# H2BR0.net
KiCad netlist of a schematic drawn in EAGLE
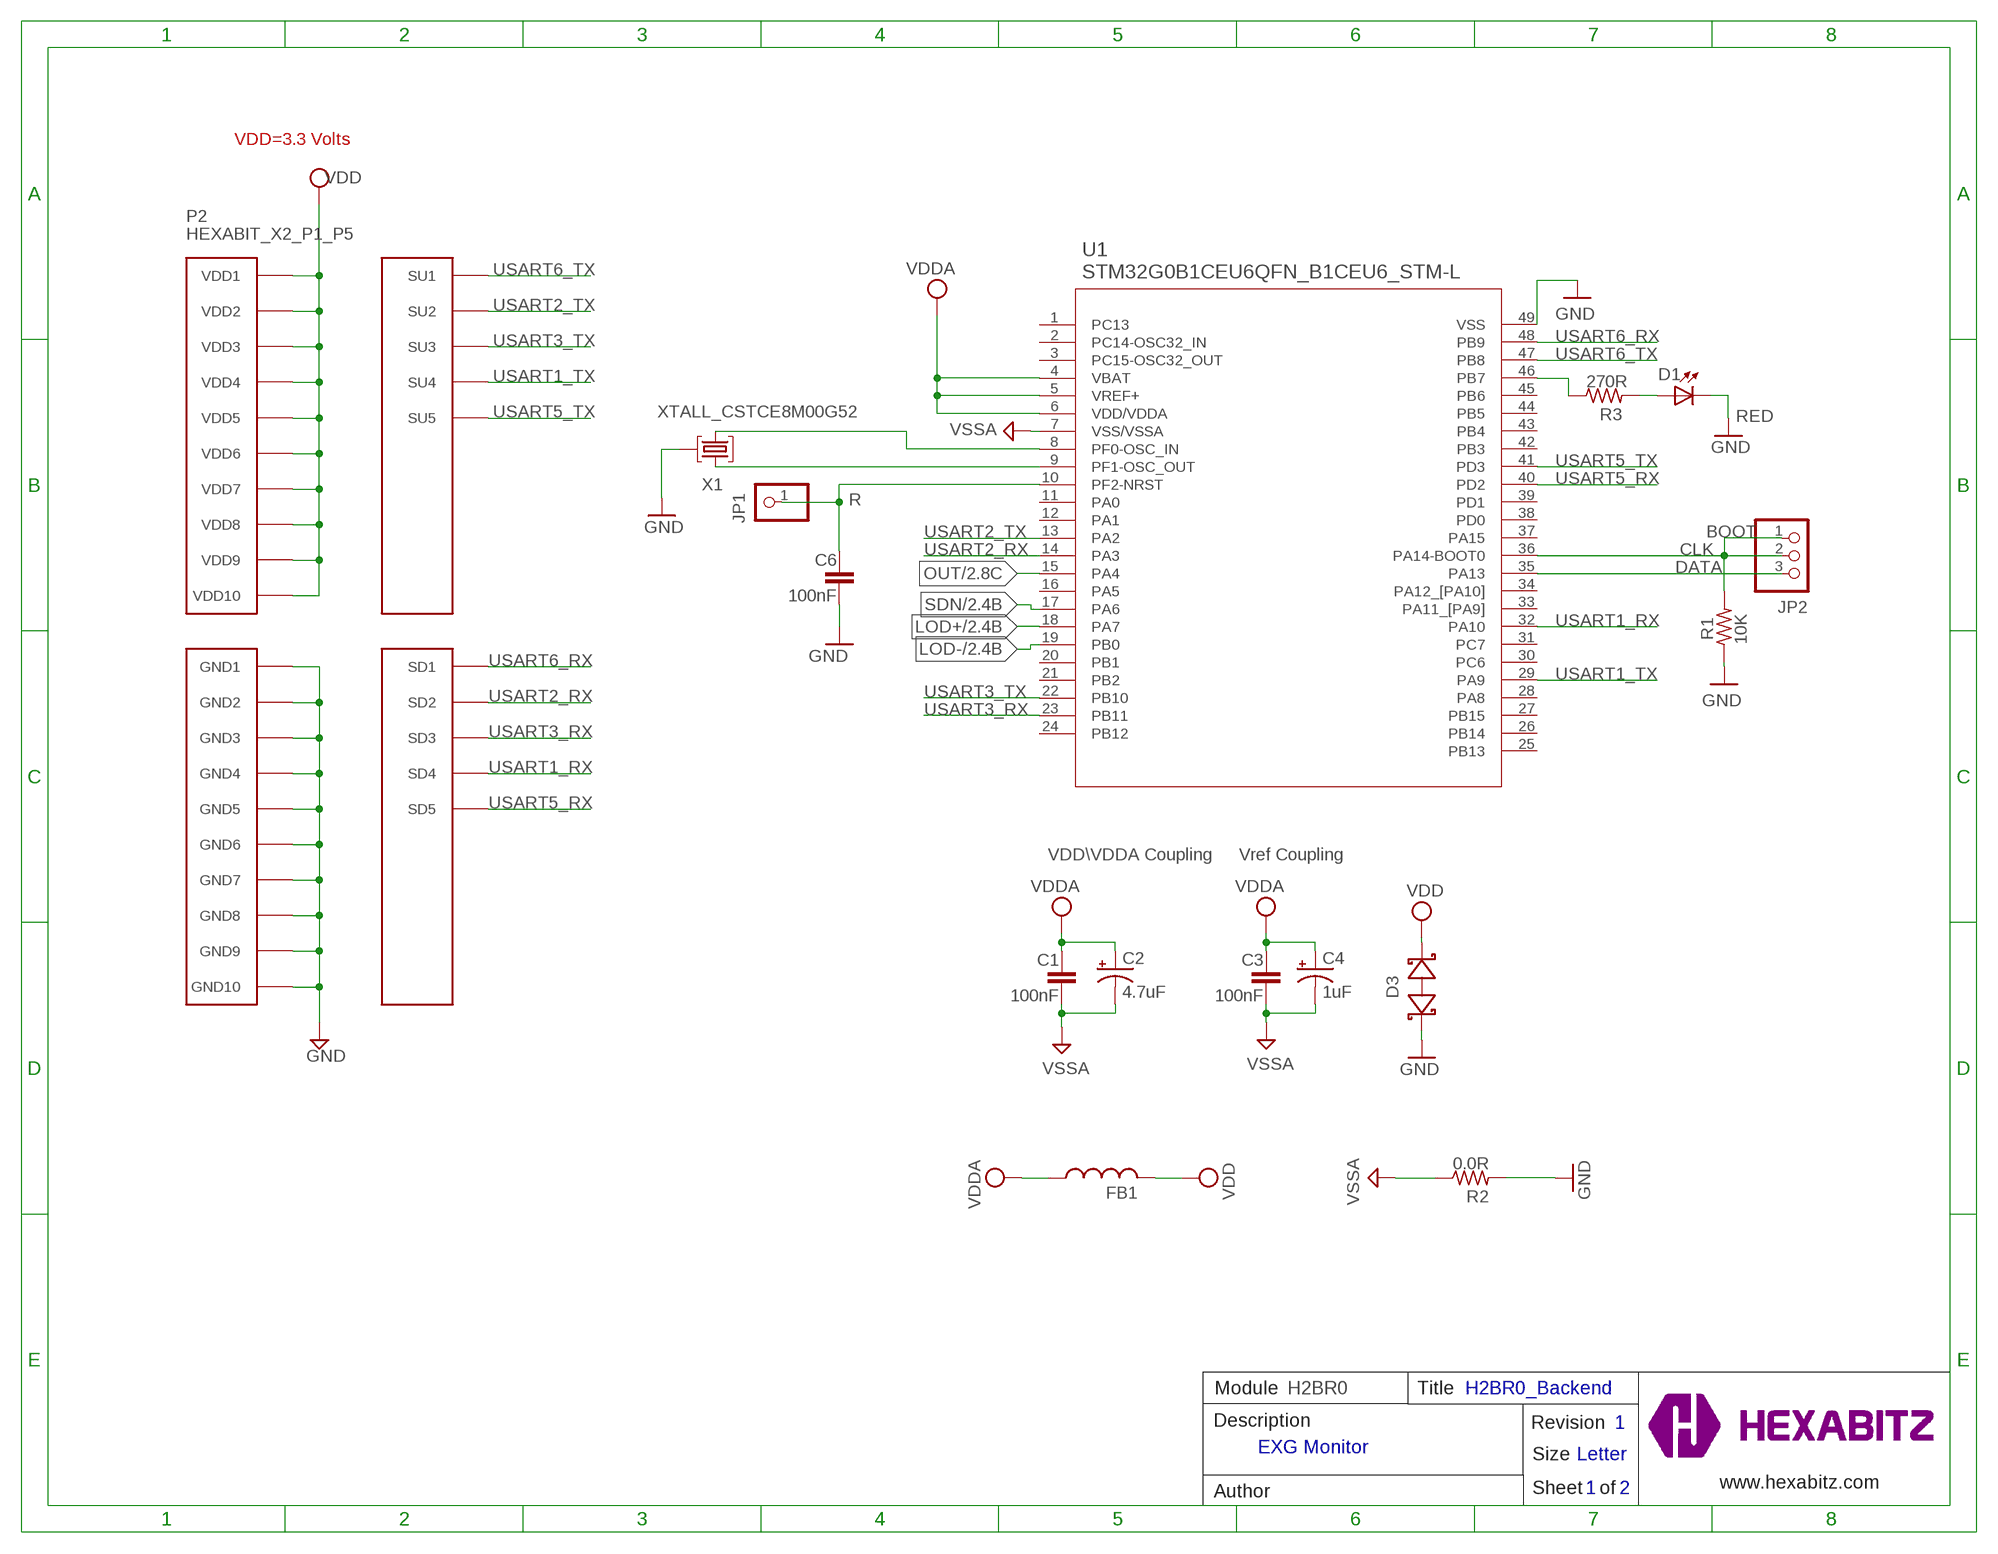
[diagram p0: schematic, sheet 1]
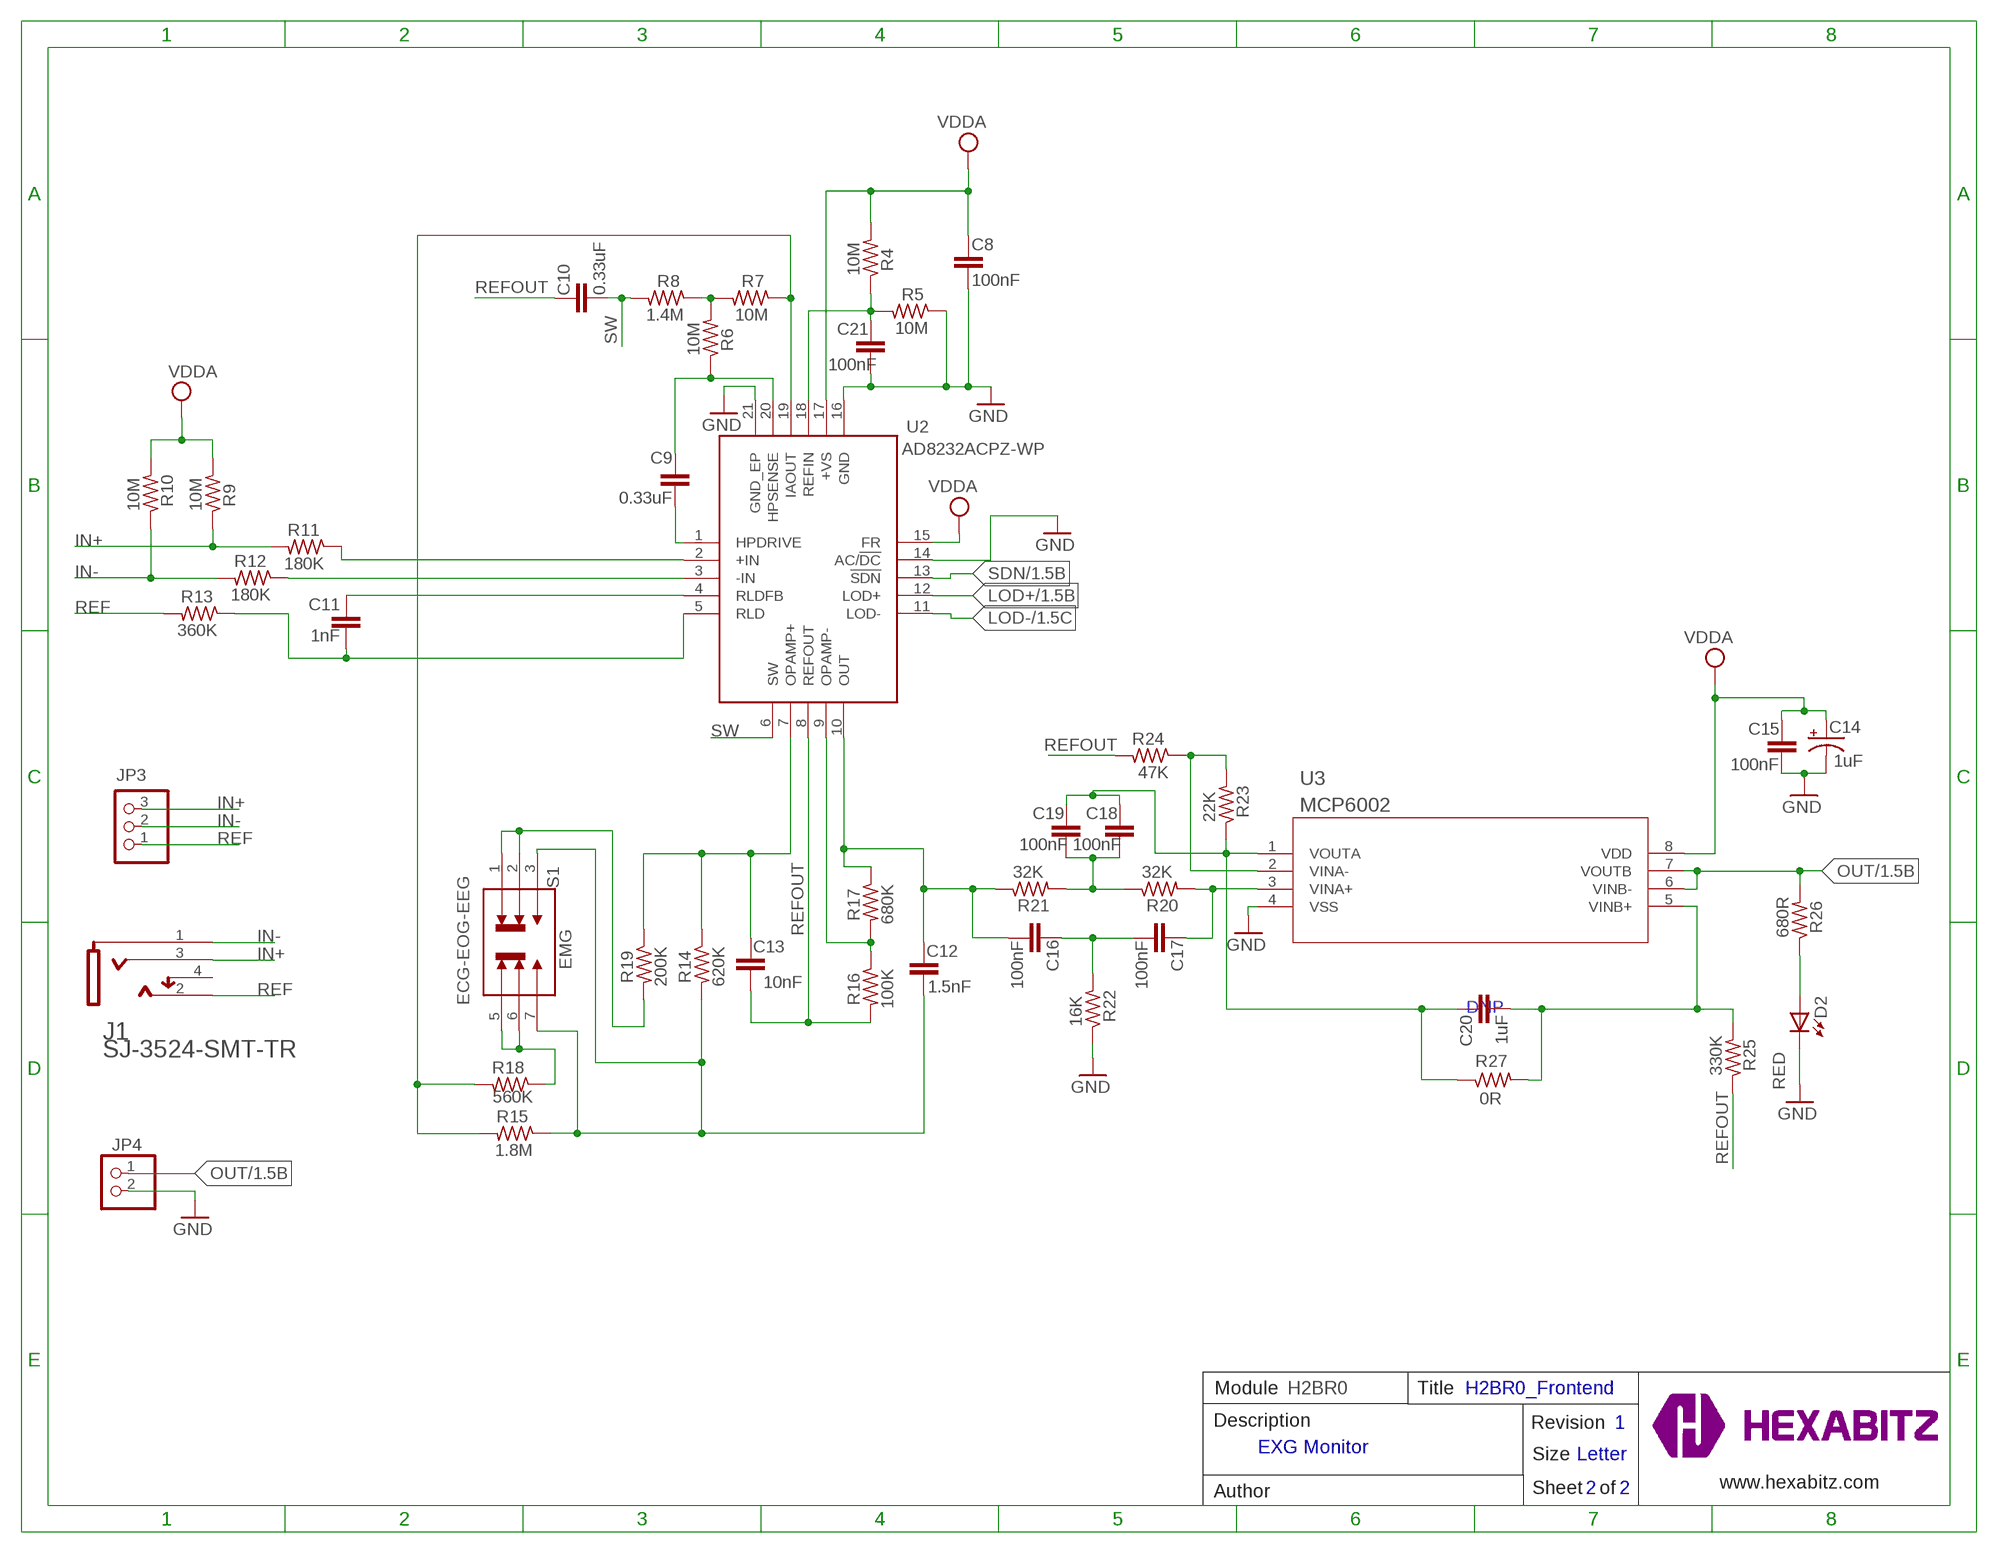
[diagram p1: schematic, sheet 2]

(export (version "E")
  (design (tool "Eeschema 10.0.6"))
  (components
    (comp (ref "C1")
      (value "100nF")
      (footprint "eagle-import:C-0603")
      (libsource (lib "eagle-import") (part "C-0603"))
    )
    (comp (ref "C2")
      (value "4.7uF")
      (footprint "eagle-import:C-0805-POL")
      (libsource (lib "eagle-import") (part "C-0805-POL"))
    )
    (comp (ref "C3")
      (value "100nF")
      (footprint "eagle-import:C-0603")
      (libsource (lib "eagle-import") (part "C-0603"))
    )
    (comp (ref "C4")
      (value "1uF")
      (footprint "eagle-import:C-0805-POL")
      (libsource (lib "eagle-import") (part "C-0805-POL"))
    )
    (comp (ref "C6")
      (value "100nF")
      (footprint "eagle-import:C-0603")
      (libsource (lib "eagle-import") (part "C-0603"))
    )
    (comp (ref "D1")
      (value "RED")
      (footprint "eagle-import:VLMS1300-GS08")
      (fields
        (field (name "MPN") "VLMS1300-GS08")
        (field (name "MFN") "Vishay")
        (field (name "MPN_1") "VLMS1300-GS08")
        (field (name "OCTOPART_URL") "https://octopart.com/vlms1300-gs08-vishay-21709201?r=sp&s=_gcP4_q8T1SC6PJQPTQ9yA")
      )
      (libsource (lib "eagle-import") (part "VLMS1300-GS08"))
    )
    (comp (ref "D3")
      (value "BOURNS_CDSOD323-T03SCBOURNS_CDSOD323-T03SC_0_0")
      (footprint "eagle-import:BOURNS_CDSOD323-T03SC_0")
      (fields (field (name "MPN") "CDSOD323-T03SC"))
      (libsource (lib "eagle-import") (part "BOURNS_CDSOD323-T03SCBOURNS_CDSOD323-T03SC_0_0"))
    )
    (comp (ref "FB1")
      (value "FB-0603")
      (footprint "eagle-import:FB-0603")
      (libsource (lib "eagle-import") (part "FB-0603"))
    )
    (comp (ref "JP1")
      (value "R")
      (footprint "eagle-import:1X01")
      (fields (field (name "MPN") "87227-1"))
      (libsource (lib "eagle-import") (part "PINHD-1X1"))
    )
    (comp (ref "JP2")
      (value "PINHD-1X3")
      (footprint "eagle-import:1X03")
      (libsource (lib "eagle-import") (part "PINHD-1X3"))
    )
    (comp (ref "P2")
      (value "HEXABIT_X2_P1_P5")
      (footprint "eagle-import:HEXABIT_17.32_X2_P1_P5")
      (libsource (lib "eagle-import") (part "HEXABIT_X2_P1_P5"))
    )
    (comp (ref "R1")
      (value "10K")
      (footprint "eagle-import:R-0603")
      (libsource (lib "eagle-import") (part "R-0603"))
    )
    (comp (ref "R2")
      (value "0.0R")
      (footprint "eagle-import:R-0603")
      (libsource (lib "eagle-import") (part "R-0603"))
    )
    (comp (ref "R3")
      (value "270R")
      (footprint "eagle-import:R-0603")
      (libsource (lib "eagle-import") (part "R-0603"))
    )
    (comp (ref "TRIMBLE-LOGO2")
      (value "HEXA-LOGO")
      (footprint "eagle-import:HEXA-LOGO")
      (libsource (lib "eagle-import") (part "HEXA-LOGO"))
    )
    (comp (ref "U1")
      (value "STM32G0B1CEU6QFN_B1CEU6_STM-L")
      (footprint "eagle-import:QFN_B1CEU6_STM-L")
      (fields
        (field (name "MANUFACTURER_PART_NUMBER") "STM32G0B1CEU6")
        (field (name "COPYRIGHT") "Copyright (C) 2021 Ultra Librarian. All rights reserved.")
      )
      (libsource (lib "eagle-import") (part "STM32G0B1CEU6QFN_B1CEU6_STM-L"))
    )
    (comp (ref "X1")
      (value "XTALL_CSTCE8M00G52")
      (footprint "eagle-import:XTALL_CSTCE8M00G52")
      (fields (field (name "MPN") "CSTCE8M00G52Z-R0"))
      (libsource (lib "eagle-import") (part "XTALL_CSTCE8M00G52"))
    )
    (comp (ref "C8")
      (value "100nF")
      (footprint "eagle-import:C-0603")
      (libsource (lib "eagle-import") (part "C-0603"))
    )
    (comp (ref "C9")
      (value "0.33uF")
      (footprint "eagle-import:C-0603")
      (libsource (lib "eagle-import") (part "C-0603"))
    )
    (comp (ref "C10")
      (value "0.33uF")
      (footprint "eagle-import:C-0603")
      (libsource (lib "eagle-import") (part "C-0603"))
    )
    (comp (ref "C11")
      (value "1nF")
      (footprint "eagle-import:C-0603")
      (libsource (lib "eagle-import") (part "C-0603"))
    )
    (comp (ref "C12")
      (value "1.5nF")
      (footprint "eagle-import:C-0603")
      (libsource (lib "eagle-import") (part "C-0603"))
    )
    (comp (ref "C13")
      (value "10nF")
      (footprint "eagle-import:C-0603")
      (libsource (lib "eagle-import") (part "C-0603"))
    )
    (comp (ref "C14")
      (value "1uF")
      (footprint "eagle-import:C-0805-POL")
      (libsource (lib "eagle-import") (part "C-0805-POL"))
    )
    (comp (ref "C15")
      (value "100nF")
      (footprint "eagle-import:C-0603")
      (libsource (lib "eagle-import") (part "C-0603"))
    )
    (comp (ref "C16")
      (value "100nF")
      (footprint "eagle-import:C-0603")
      (libsource (lib "eagle-import") (part "C-0603"))
    )
    (comp (ref "C17")
      (value "100nF")
      (footprint "eagle-import:C-0603")
      (libsource (lib "eagle-import") (part "C-0603"))
    )
    (comp (ref "C18")
      (value "100nF")
      (footprint "eagle-import:C-0603")
      (libsource (lib "eagle-import") (part "C-0603"))
    )
    (comp (ref "C19")
      (value "100nF")
      (footprint "eagle-import:C-0603")
      (libsource (lib "eagle-import") (part "C-0603"))
    )
    (comp (ref "C20")
      (value "1uF")
      (footprint "eagle-import:C-0603")
      (fields (field (name "MPN") "GRM188R61A105KA61J"))
      (libsource (lib "eagle-import") (part "C-0603"))
    )
    (comp (ref "C21")
      (value "100nF")
      (footprint "eagle-import:C-0603")
      (libsource (lib "eagle-import") (part "C-0603"))
    )
    (comp (ref "D2")
      (value "RED")
      (footprint "eagle-import:VLMS1300-GS08")
      (fields
        (field (name "MPN") "VLMS1300-GS08")
        (field (name "MFN") "Vishay")
        (field (name "MPN_1") "VLMS1300-GS08")
        (field (name "OCTOPART_URL") "https://octopart.com/vlms1300-gs08-vishay-21709201?r=sp&s=_gcP4_q8T1SC6PJQPTQ9yA")
      )
      (libsource (lib "eagle-import") (part "VLMS1300-GS08"))
    )
    (comp (ref "J1")
      (value "CUI_DEVICES_SJ-3524-SMT-TRCUI_DEVICES_SJ-3524-SMT-TR_0_0")
      (footprint "eagle-import:CUI_DEVICES_SJ-3524-SMT-TR_0")
      (fields
        (field (name "DIGIKEY_PART_NUMBER") "CP-3524SJCT-ND")
        (field (name "MOUSER_PART_NUMBER") "490-SJ-3524-SMT-TR")
        (field (name "MPN") "SJ-3524-SMT-TR")
      )
      (libsource (lib "eagle-import") (part "CUI_DEVICES_SJ-3524-SMT-TRCUI_DEVICES_SJ-3524-SMT-TR_0_0"))
    )
    (comp (ref "JP3")
      (value "PINHD-1X3")
      (footprint "eagle-import:1X03")
      (libsource (lib "eagle-import") (part "PINHD-1X3"))
    )
    (comp (ref "JP4")
      (value "PINHD-1X2(ROUND)")
      (footprint "eagle-import:1X02")
      (libsource (lib "eagle-import") (part "PINHD-1X2(ROUND)"))
    )
    (comp (ref "R4")
      (value "10M")
      (footprint "eagle-import:R-0603")
      (libsource (lib "eagle-import") (part "R-0603"))
    )
    (comp (ref "R5")
      (value "10M")
      (footprint "eagle-import:R-0603")
      (libsource (lib "eagle-import") (part "R-0603"))
    )
    (comp (ref "R6")
      (value "10M")
      (footprint "eagle-import:R-0603")
      (libsource (lib "eagle-import") (part "R-0603"))
    )
    (comp (ref "R7")
      (value "10M")
      (footprint "eagle-import:R-0603")
      (libsource (lib "eagle-import") (part "R-0603"))
    )
    (comp (ref "R8")
      (value "1.4M")
      (footprint "eagle-import:R-0603")
      (libsource (lib "eagle-import") (part "R-0603"))
    )
    (comp (ref "R9")
      (value "10M")
      (footprint "eagle-import:R-0603")
      (libsource (lib "eagle-import") (part "R-0603"))
    )
    (comp (ref "R10")
      (value "10M")
      (footprint "eagle-import:R-0603")
      (libsource (lib "eagle-import") (part "R-0603"))
    )
    (comp (ref "R11")
      (value "180K")
      (footprint "eagle-import:R-0603")
      (libsource (lib "eagle-import") (part "R-0603"))
    )
    (comp (ref "R12")
      (value "180K")
      (footprint "eagle-import:R-0603")
      (libsource (lib "eagle-import") (part "R-0603"))
    )
    (comp (ref "R13")
      (value "360K")
      (footprint "eagle-import:R-0603")
      (libsource (lib "eagle-import") (part "R-0603"))
    )
    (comp (ref "R14")
      (value "620K")
      (footprint "eagle-import:R-0603")
      (libsource (lib "eagle-import") (part "R-0603"))
    )
    (comp (ref "R15")
      (value "1.8M")
      (footprint "eagle-import:R-0603")
      (libsource (lib "eagle-import") (part "R-0603"))
    )
    (comp (ref "R16")
      (value "100K")
      (footprint "eagle-import:R-0603")
      (libsource (lib "eagle-import") (part "R-0603"))
    )
    (comp (ref "R17")
      (value "680K")
      (footprint "eagle-import:R-0603")
      (libsource (lib "eagle-import") (part "R-0603"))
    )
    (comp (ref "R18")
      (value "560K")
      (footprint "eagle-import:R-0603")
      (libsource (lib "eagle-import") (part "R-0603"))
    )
    (comp (ref "R19")
      (value "200K")
      (footprint "eagle-import:R-0603")
      (libsource (lib "eagle-import") (part "R-0603"))
    )
    (comp (ref "R20")
      (value "32K")
      (footprint "eagle-import:R-0603")
      (libsource (lib "eagle-import") (part "R-0603"))
    )
    (comp (ref "R21")
      (value "32K")
      (footprint "eagle-import:R-0603")
      (libsource (lib "eagle-import") (part "R-0603"))
    )
    (comp (ref "R22")
      (value "16K")
      (footprint "eagle-import:R-0603")
      (libsource (lib "eagle-import") (part "R-0603"))
    )
    (comp (ref "R23")
      (value "22K")
      (footprint "eagle-import:R-0603")
      (libsource (lib "eagle-import") (part "R-0603"))
    )
    (comp (ref "R24")
      (value "47K")
      (footprint "eagle-import:R-0603")
      (libsource (lib "eagle-import") (part "R-0603"))
    )
    (comp (ref "R25")
      (value "330K")
      (footprint "eagle-import:R-0603")
      (libsource (lib "eagle-import") (part "R-0603"))
    )
    (comp (ref "R26")
      (value "680R")
      (footprint "eagle-import:R-0603")
      (libsource (lib "eagle-import") (part "R-0603"))
    )
    (comp (ref "R27")
      (value "0R")
      (footprint "eagle-import:R-0603")
      (libsource (lib "eagle-import") (part "R-0603"))
    )
    (comp (ref "S1")
      (value "JS202011JCQN")
      (footprint "eagle-import:SW_JS202011JCQN")
      (fields (field (name "DIGI-KEY_PART_NUMBER") "CKN10723TR-ND") (field (name "MF") "C&K"))
      (libsource (lib "eagle-import") (part "JS202011JCQN"))
    )
    (comp (ref "U2")
      (value "AD8232ACPZ-WP")
      (footprint "eagle-import:QFN50P400X400X80-21N")
      (fields (field (name "MOUSER_PART_NUMBER") "584-AD8232ACPZ-WP"))
      (libsource (lib "eagle-import") (part "AD8232ACPZ-WP"))
    )
    (comp (ref "U3")
      (value "MCP6002")
      (footprint "eagle-import:SOIC8-N_MC_MCH-L")
      (fields
        (field (name "MANUFACTURER_PART_NUMBER") "MCP6002-I/SN")
        (field (name "COPYRIGHT") "Copyright (C) 2022 Ultra Librarian. All rights reserved.")
      )
      (libsource (lib "eagle-import") (part "MCP6002-I/SNSOIC8-N_MC_MCH-L"))
    )
  )
  (nets
    (net (code "1") (name "CLK") (class "Default")
      (node (ref "JP2") (pin "1") (pinfunction "1_1") (pintype "passive"))
      (node (ref "JP2") (pin "2") (pinfunction "2_2") (pintype "passive"))
      (node (ref "R1") (pin "2") (pinfunction "2_2") (pintype "passive"))
      (node (ref "U1") (pin "36") (pinfunction "PA14-BOOT0_36") (pintype "bidirectional"))
    )
    (net (code "2") (name "DATA") (class "Default")
      (node (ref "JP2") (pin "3") (pinfunction "3_3") (pintype "passive"))
      (node (ref "U1") (pin "35") (pinfunction "PA13_35") (pintype "bidirectional"))
    )
    (net (code "3") (name "GND") (class "Default")
      (node (ref "C14") (pin "2") (pinfunction "-_2") (pintype "passive"))
      (node (ref "C15") (pin "2") (pinfunction "2_2") (pintype "passive"))
      (node (ref "C21") (pin "2") (pinfunction "2_2") (pintype "passive"))
      (node (ref "C6") (pin "2") (pinfunction "2_2") (pintype "passive"))
      (node (ref "C8") (pin "2") (pinfunction "2_2") (pintype "passive"))
      (node (ref "D1") (pin "C") (pinfunction "C_C") (pintype "passive"))
      (node (ref "D2") (pin "C") (pinfunction "C_C") (pintype "passive"))
      (node (ref "D3") (pin "1") (pinfunction "A_1") (pintype "passive"))
      (node (ref "JP4") (pin "2") (pinfunction "2_2") (pintype "passive"))
      (node (ref "P2") (pin "PAD_PD11") (pinfunction "GND1_PAD_PD11") (pintype "power_in"))
      (node (ref "P2") (pin "PAD_PD12") (pinfunction "GND2_PAD_PD12") (pintype "power_in"))
      (node (ref "P2") (pin "PAD_PD13") (pinfunction "GND3_PAD_PD13") (pintype "power_in"))
      (node (ref "P2") (pin "PAD_PD14") (pinfunction "GND4_PAD_PD14") (pintype "power_in"))
      (node (ref "P2") (pin "PAD_PD15") (pinfunction "GND5_PAD_PD15") (pintype "power_in"))
      (node (ref "P2") (pin "PAD_PD16") (pinfunction "GND6_PAD_PD16") (pintype "power_in"))
      (node (ref "P2") (pin "PAD_PD17") (pinfunction "GND7_PAD_PD17") (pintype "power_in"))
      (node (ref "P2") (pin "PAD_PD18") (pinfunction "GND8_PAD_PD18") (pintype "power_in"))
      (node (ref "P2") (pin "PAD_PD19") (pinfunction "GND9_PAD_PD19") (pintype "power_in"))
      (node (ref "P2") (pin "PAD_PD20") (pinfunction "GND10_PAD_PD20") (pintype "power_in"))
      (node (ref "R1") (pin "1") (pinfunction "1_1") (pintype "passive"))
      (node (ref "R2") (pin "2") (pinfunction "2_2") (pintype "passive"))
      (node (ref "R22") (pin "1") (pinfunction "1_1") (pintype "passive"))
      (node (ref "R5") (pin "1") (pinfunction "1_1") (pintype "passive"))
      (node (ref "U1") (pin "49") (pinfunction "VSS_49") (pintype "passive"))
      (node (ref "U2") (pin "14") (pinfunction "AC/~{DC}_14") (pintype "bidirectional"))
      (node (ref "U2") (pin "16") (pinfunction "GND_16") (pintype "power_in"))
      (node (ref "U2") (pin "21") (pinfunction "GND_EP_21") (pintype "power_in"))
      (node (ref "U3") (pin "4") (pinfunction "VSS_4") (pintype "passive"))
      (node (ref "X1") (pin "P$2") (pinfunction "2_P$2") (pintype "passive"))
    )
    (net (code "4") (name "IN+") (class "Default")
      (node (ref "J1") (pin "3") (pinfunction "RING_3") (pintype "passive"))
      (node (ref "JP3") (pin "3") (pinfunction "3_3") (pintype "passive"))
      (node (ref "R11") (pin "2") (pinfunction "2_2") (pintype "passive"))
      (node (ref "R9") (pin "1") (pinfunction "1_1") (pintype "passive"))
    )
    (net (code "5") (name "IN-") (class "Default")
      (node (ref "J1") (pin "1") (pinfunction "SLEEVE_1") (pintype "passive"))
      (node (ref "JP3") (pin "2") (pinfunction "2_2") (pintype "passive"))
      (node (ref "R10") (pin "1") (pinfunction "1_1") (pintype "passive"))
      (node (ref "R12") (pin "2") (pinfunction "2_2") (pintype "passive"))
    )
    (net (code "6") (name "LOD+") (class "Default")
      (node (ref "U1") (pin "18") (pinfunction "PA7_18") (pintype "bidirectional"))
      (node (ref "U2") (pin "12") (pinfunction "LOD+_12") (pintype "bidirectional"))
    )
    (net (code "7") (name "LOD-") (class "Default")
      (node (ref "U1") (pin "19") (pinfunction "PB0_19") (pintype "bidirectional"))
      (node (ref "U2") (pin "11") (pinfunction "LOD-_11") (pintype "bidirectional"))
    )
    (net (code "8") (name "Net-(C12-Pad2)") (class "Default")
      (node (ref "C12") (pin "2") (pinfunction "2_2") (pintype "passive"))
      (node (ref "R14") (pin "2") (pinfunction "2_2") (pintype "passive"))
      (node (ref "R15") (pin "1") (pinfunction "1_1") (pintype "passive"))
      (node (ref "S1") (pin "3") (pinfunction "3_3") (pintype "passive"))
      (node (ref "S1") (pin "7") (pinfunction "7_7") (pintype "passive"))
    )
    (net (code "9") (name "Net-(C16-Pad1)") (class "Default")
      (node (ref "C16") (pin "1") (pinfunction "1_1") (pintype "passive"))
      (node (ref "C17") (pin "2") (pinfunction "2_2") (pintype "passive"))
      (node (ref "R22") (pin "2") (pinfunction "2_2") (pintype "passive"))
    )
    (net (code "10") (name "Net-(C18-Pad2)") (class "Default")
      (node (ref "C18") (pin "2") (pinfunction "2_2") (pintype "passive"))
      (node (ref "C19") (pin "2") (pinfunction "2_2") (pintype "passive"))
      (node (ref "R20") (pin "1") (pinfunction "1_1") (pintype "passive"))
      (node (ref "R21") (pin "2") (pinfunction "2_2") (pintype "passive"))
    )
    (net (code "11") (name "Net-(D1-PadA)") (class "Default")
      (node (ref "D1") (pin "A") (pinfunction "A_A") (pintype "passive"))
      (node (ref "R3") (pin "2") (pinfunction "2_2") (pintype "passive"))
    )
    (net (code "12") (name "Net-(D2-PadA)") (class "Default")
      (node (ref "D2") (pin "A") (pinfunction "A_A") (pintype "passive"))
      (node (ref "R26") (pin "1") (pinfunction "1_1") (pintype "passive"))
    )
    (net (code "13") (name "Net-(R6-Pad2)") (class "Default")
      (node (ref "R6") (pin "2") (pinfunction "2_2") (pintype "passive"))
      (node (ref "R7") (pin "2") (pinfunction "2_2") (pintype "passive"))
      (node (ref "R8") (pin "1") (pinfunction "1_1") (pintype "passive"))
    )
    (net (code "14") (name "Net-(R18-Pad1)") (class "Default")
      (node (ref "R18") (pin "1") (pinfunction "1_1") (pintype "passive"))
      (node (ref "S1") (pin "5") (pinfunction "5_5") (pintype "passive"))
      (node (ref "S1") (pin "6") (pinfunction "6_6") (pintype "passive"))
    )
    (net (code "15") (name "Net-(R19-Pad2)") (class "Default")
      (node (ref "R19") (pin "2") (pinfunction "2_2") (pintype "passive"))
      (node (ref "S1") (pin "1") (pinfunction "1_1") (pintype "passive"))
      (node (ref "S1") (pin "2") (pinfunction "2_2") (pintype "passive"))
    )
    (net (code "16") (name "Net-(U1-PB7)") (class "Default")
      (node (ref "R3") (pin "1") (pinfunction "1_1") (pintype "passive"))
      (node (ref "U1") (pin "46") (pinfunction "PB7_46") (pintype "bidirectional"))
    )
    (net (code "17") (name "Net-(U1-PF0-OSC_IN)") (class "Default")
      (node (ref "U1") (pin "8") (pinfunction "PF0-OSC_IN_8") (pintype "bidirectional"))
      (node (ref "X1") (pin "P$3") (pinfunction "3_P$3") (pintype "passive"))
    )
    (net (code "18") (name "Net-(U1-PF1-OSC_OUT)") (class "Default")
      (node (ref "U1") (pin "9") (pinfunction "PF1-OSC_OUT_9") (pintype "output"))
      (node (ref "X1") (pin "P$1") (pinfunction "1_P$1") (pintype "passive"))
    )
    (net (code "19") (name "Net-(U1-PF2-NRST)") (class "Default")
      (node (ref "C6") (pin "1") (pinfunction "1_1") (pintype "passive"))
      (node (ref "JP1") (pin "1") (pinfunction "1_1") (pintype "passive"))
      (node (ref "U1") (pin "10") (pinfunction "PF2-NRST_10") (pintype "bidirectional"))
    )
    (net (code "20") (name "Net-(U2-+IN)") (class "Default")
      (node (ref "R11") (pin "1") (pinfunction "1_1") (pintype "passive"))
      (node (ref "U2") (pin "2") (pinfunction "+IN_2") (pintype "input"))
    )
    (net (code "21") (name "Net-(U2--IN)") (class "Default")
      (node (ref "R12") (pin "1") (pinfunction "1_1") (pintype "passive"))
      (node (ref "U2") (pin "3") (pinfunction "-IN_3") (pintype "input"))
    )
    (net (code "22") (name "Net-(U2-HPDRIVE)") (class "Default")
      (node (ref "C9") (pin "2") (pinfunction "2_2") (pintype "passive"))
      (node (ref "U2") (pin "1") (pinfunction "HPDRIVE_1") (pintype "bidirectional"))
    )
    (net (code "23") (name "Net-(U2-HPSENSE)") (class "Default")
      (node (ref "C9") (pin "1") (pinfunction "1_1") (pintype "passive"))
      (node (ref "R6") (pin "1") (pinfunction "1_1") (pintype "passive"))
      (node (ref "U2") (pin "20") (pinfunction "HPSENSE_20") (pintype "bidirectional"))
    )
    (net (code "24") (name "Net-(U2-IAOUT)") (class "Default")
      (node (ref "R15") (pin "2") (pinfunction "2_2") (pintype "passive"))
      (node (ref "R18") (pin "2") (pinfunction "2_2") (pintype "passive"))
      (node (ref "R7") (pin "1") (pinfunction "1_1") (pintype "passive"))
      (node (ref "U2") (pin "19") (pinfunction "IAOUT_19") (pintype "output"))
    )
    (net (code "25") (name "Net-(U2-OPAMP+)") (class "Default")
      (node (ref "C13") (pin "1") (pinfunction "1_1") (pintype "passive"))
      (node (ref "R14") (pin "1") (pinfunction "1_1") (pintype "passive"))
      (node (ref "R19") (pin "1") (pinfunction "1_1") (pintype "passive"))
      (node (ref "U2") (pin "7") (pinfunction "OPAMP+_7") (pintype "bidirectional"))
    )
    (net (code "26") (name "Net-(U2-OPAMP-)") (class "Default")
      (node (ref "R16") (pin "1") (pinfunction "1_1") (pintype "passive"))
      (node (ref "R17") (pin "2") (pinfunction "2_2") (pintype "passive"))
      (node (ref "U2") (pin "9") (pinfunction "OPAMP-_9") (pintype "bidirectional"))
    )
    (net (code "27") (name "Net-(U2-OUT)") (class "Default")
      (node (ref "C12") (pin "1") (pinfunction "1_1") (pintype "passive"))
      (node (ref "C16") (pin "2") (pinfunction "2_2") (pintype "passive"))
      (node (ref "R17") (pin "1") (pinfunction "1_1") (pintype "passive"))
      (node (ref "R21") (pin "1") (pinfunction "1_1") (pintype "passive"))
      (node (ref "U2") (pin "10") (pinfunction "OUT_10") (pintype "output"))
    )
    (net (code "28") (name "Net-(U2-REFIN)") (class "Default")
      (node (ref "C21") (pin "1") (pinfunction "1_1") (pintype "passive"))
      (node (ref "R4") (pin "1") (pinfunction "1_1") (pintype "passive"))
      (node (ref "R5") (pin "2") (pinfunction "2_2") (pintype "passive"))
      (node (ref "U2") (pin "18") (pinfunction "REFIN_18") (pintype "input"))
    )
    (net (code "29") (name "Net-(U2-RLD)") (class "Default")
      (node (ref "C11") (pin "2") (pinfunction "2_2") (pintype "passive"))
      (node (ref "R13") (pin "1") (pinfunction "1_1") (pintype "passive"))
      (node (ref "U2") (pin "5") (pinfunction "RLD_5") (pintype "bidirectional"))
    )
    (net (code "30") (name "Net-(U2-RLDFB)") (class "Default")
      (node (ref "C11") (pin "1") (pinfunction "1_1") (pintype "passive"))
      (node (ref "U2") (pin "4") (pinfunction "RLDFB_4") (pintype "bidirectional"))
    )
    (net (code "31") (name "Net-(U3-VINA+)") (class "Default")
      (node (ref "C17") (pin "1") (pinfunction "1_1") (pintype "passive"))
      (node (ref "R20") (pin "2") (pinfunction "2_2") (pintype "passive"))
      (node (ref "U3") (pin "3") (pinfunction "VINA+_3") (pintype "input"))
    )
    (net (code "32") (name "Net-(U3-VINA-)") (class "Default")
      (node (ref "R23") (pin "2") (pinfunction "2_2") (pintype "passive"))
      (node (ref "R24") (pin "1") (pinfunction "1_1") (pintype "passive"))
      (node (ref "U3") (pin "2") (pinfunction "VINA-_2") (pintype "input"))
    )
    (net (code "33") (name "Net-(U3-VINB+)") (class "Default")
      (node (ref "C20") (pin "2") (pinfunction "2_2") (pintype "passive"))
      (node (ref "R25") (pin "2") (pinfunction "2_2") (pintype "passive"))
      (node (ref "R27") (pin "2") (pinfunction "2_2") (pintype "passive"))
      (node (ref "U3") (pin "5") (pinfunction "VINB+_5") (pintype "input"))
    )
    (net (code "34") (name "Net-(U3-VOUTA)") (class "Default")
      (node (ref "C18") (pin "1") (pinfunction "1_1") (pintype "passive"))
      (node (ref "C19") (pin "1") (pinfunction "1_1") (pintype "passive"))
      (node (ref "C20") (pin "1") (pinfunction "1_1") (pintype "passive"))
      (node (ref "R23") (pin "1") (pinfunction "1_1") (pintype "passive"))
      (node (ref "R27") (pin "1") (pinfunction "1_1") (pintype "passive"))
      (node (ref "U3") (pin "1") (pinfunction "VOUTA_1") (pintype "output"))
    )
    (net (code "35") (name "OUT") (class "Default")
      (node (ref "JP4") (pin "1") (pinfunction "1_1") (pintype "passive"))
      (node (ref "R26") (pin "2") (pinfunction "2_2") (pintype "passive"))
      (node (ref "U1") (pin "15") (pinfunction "PA4_15") (pintype "bidirectional"))
      (node (ref "U3") (pin "6") (pinfunction "VINB-_6") (pintype "input"))
      (node (ref "U3") (pin "7") (pinfunction "VOUTB_7") (pintype "output"))
    )
    (net (code "36") (name "REF") (class "Default")
      (node (ref "J1") (pin "2") (pinfunction "TIP_2") (pintype "passive"))
      (node (ref "JP3") (pin "1") (pinfunction "1_1") (pintype "passive"))
      (node (ref "R13") (pin "2") (pinfunction "2_2") (pintype "passive"))
    )
    (net (code "37") (name "REFOUT") (class "Default")
      (node (ref "C10") (pin "1") (pinfunction "1_1") (pintype "passive"))
      (node (ref "C13") (pin "2") (pinfunction "2_2") (pintype "passive"))
      (node (ref "R16") (pin "2") (pinfunction "2_2") (pintype "passive"))
      (node (ref "R24") (pin "2") (pinfunction "2_2") (pintype "passive"))
      (node (ref "R25") (pin "1") (pinfunction "1_1") (pintype "passive"))
      (node (ref "U2") (pin "8") (pinfunction "REFOUT_8") (pintype "output"))
    )
    (net (code "38") (name "SDN") (class "Default")
      (node (ref "U1") (pin "17") (pinfunction "PA6_17") (pintype "bidirectional"))
      (node (ref "U2") (pin "13") (pinfunction "~{SDN}_13") (pintype "bidirectional"))
    )
    (net (code "39") (name "SW") (class "Default")
      (node (ref "C10") (pin "2") (pinfunction "2_2") (pintype "passive"))
      (node (ref "R8") (pin "2") (pinfunction "2_2") (pintype "passive"))
      (node (ref "U2") (pin "6") (pinfunction "SW_6") (pintype "bidirectional"))
    )
    (net (code "40") (name "USART1_RX") (class "Default")
      (node (ref "P2") (pin "PAD_PD4") (pinfunction "SD4_PAD_PD4") (pintype "bidirectional"))
      (node (ref "U1") (pin "32") (pinfunction "PA10_32") (pintype "bidirectional"))
    )
    (net (code "41") (name "USART1_TX") (class "Default")
      (node (ref "P2") (pin "PAD_PU4") (pinfunction "SU4_PAD_PU4") (pintype "bidirectional"))
      (node (ref "U1") (pin "29") (pinfunction "PA9_29") (pintype "bidirectional"))
    )
    (net (code "42") (name "USART2_RX") (class "Default")
      (node (ref "P2") (pin "PAD_PD2") (pinfunction "SD2_PAD_PD2") (pintype "bidirectional"))
      (node (ref "U1") (pin "14") (pinfunction "PA3_14") (pintype "bidirectional"))
    )
    (net (code "43") (name "USART2_TX") (class "Default")
      (node (ref "P2") (pin "PAD_PU2") (pinfunction "SU2_PAD_PU2") (pintype "bidirectional"))
      (node (ref "U1") (pin "13") (pinfunction "PA2_13") (pintype "bidirectional"))
    )
    (net (code "44") (name "USART3_RX") (class "Default")
      (node (ref "P2") (pin "PAD_PD3") (pinfunction "SD3_PAD_PD3") (pintype "bidirectional"))
      (node (ref "U1") (pin "23") (pinfunction "PB11_23") (pintype "bidirectional"))
    )
    (net (code "45") (name "USART3_TX") (class "Default")
      (node (ref "P2") (pin "PAD_PU3") (pinfunction "SU3_PAD_PU3") (pintype "bidirectional"))
      (node (ref "U1") (pin "22") (pinfunction "PB10_22") (pintype "bidirectional"))
    )
    (net (code "46") (name "USART5_RX") (class "Default")
      (node (ref "P2") (pin "PAD_PD5") (pinfunction "SD5_PAD_PD5") (pintype "bidirectional"))
      (node (ref "U1") (pin "40") (pinfunction "PD2_40") (pintype "bidirectional"))
    )
    (net (code "47") (name "USART5_TX") (class "Default")
      (node (ref "P2") (pin "PAD_PU5") (pinfunction "SU5_PAD_PU5") (pintype "bidirectional"))
      (node (ref "U1") (pin "41") (pinfunction "PD3_41") (pintype "bidirectional"))
    )
    (net (code "48") (name "USART6_RX") (class "Default")
      (node (ref "P2") (pin "PAD_PD1") (pinfunction "SD1_PAD_PD1") (pintype "bidirectional"))
      (node (ref "U1") (pin "48") (pinfunction "PB9_48") (pintype "bidirectional"))
    )
    (net (code "49") (name "USART6_TX") (class "Default")
      (node (ref "P2") (pin "PAD_PU1") (pinfunction "SU1_PAD_PU1") (pintype "bidirectional"))
      (node (ref "U1") (pin "47") (pinfunction "PB8_47") (pintype "bidirectional"))
    )
    (net (code "50") (name "VDD") (class "Default")
      (node (ref "D3") (pin "2") (pinfunction "C_2") (pintype "passive"))
      (node (ref "FB1") (pin "2") (pinfunction "2_2") (pintype "passive"))
      (node (ref "P2") (pin "PAD_PU11") (pinfunction "VDD1_PAD_PU11") (pintype "power_in"))
      (node (ref "P2") (pin "PAD_PU12") (pinfunction "VDD2_PAD_PU12") (pintype "power_in"))
      (node (ref "P2") (pin "PAD_PU13") (pinfunction "VDD3_PAD_PU13") (pintype "power_in"))
      (node (ref "P2") (pin "PAD_PU14") (pinfunction "VDD4_PAD_PU14") (pintype "power_in"))
      (node (ref "P2") (pin "PAD_PU15") (pinfunction "VDD5_PAD_PU15") (pintype "power_in"))
      (node (ref "P2") (pin "PAD_PU16") (pinfunction "VDD6_PAD_PU16") (pintype "power_in"))
      (node (ref "P2") (pin "PAD_PU17") (pinfunction "VDD7_PAD_PU17") (pintype "power_in"))
      (node (ref "P2") (pin "PAD_PU18") (pinfunction "VDD8_PAD_PU18") (pintype "power_in"))
      (node (ref "P2") (pin "PAD_PU19") (pinfunction "VDD9_PAD_PU19") (pintype "power_in"))
      (node (ref "P2") (pin "PAD_PU20") (pinfunction "VDD10_PAD_PU20") (pintype "power_in"))
    )
    (net (code "51") (name "VDDA") (class "Default")
      (node (ref "C1") (pin "1") (pinfunction "1_1") (pintype "passive"))
      (node (ref "C14") (pin "1") (pinfunction "+_1") (pintype "passive"))
      (node (ref "C15") (pin "1") (pinfunction "1_1") (pintype "passive"))
      (node (ref "C2") (pin "1") (pinfunction "+_1") (pintype "passive"))
      (node (ref "C3") (pin "1") (pinfunction "1_1") (pintype "passive"))
      (node (ref "C4") (pin "1") (pinfunction "+_1") (pintype "passive"))
      (node (ref "C8") (pin "1") (pinfunction "1_1") (pintype "passive"))
      (node (ref "FB1") (pin "1") (pinfunction "1_1") (pintype "passive"))
      (node (ref "R10") (pin "2") (pinfunction "2_2") (pintype "passive"))
      (node (ref "R4") (pin "2") (pinfunction "2_2") (pintype "passive"))
      (node (ref "R9") (pin "2") (pinfunction "2_2") (pintype "passive"))
      (node (ref "U1") (pin "4") (pinfunction "VBAT_4") (pintype "passive"))
      (node (ref "U1") (pin "5") (pinfunction "VREF+_5") (pintype "power_in"))
      (node (ref "U1") (pin "6") (pinfunction "VDD/VDDA_6") (pintype "power_in"))
      (node (ref "U2") (pin "15") (pinfunction "FR_15") (pintype "bidirectional"))
      (node (ref "U2") (pin "17") (pinfunction "+VS_17") (pintype "bidirectional"))
      (node (ref "U3") (pin "8") (pinfunction "VDD_8") (pintype "passive"))
    )
    (net (code "52") (name "VSSA") (class "Default")
      (node (ref "C1") (pin "2") (pinfunction "2_2") (pintype "passive"))
      (node (ref "C2") (pin "2") (pinfunction "-_2") (pintype "passive"))
      (node (ref "C3") (pin "2") (pinfunction "2_2") (pintype "passive"))
      (node (ref "C4") (pin "2") (pinfunction "-_2") (pintype "passive"))
      (node (ref "R2") (pin "1") (pinfunction "1_1") (pintype "passive"))
      (node (ref "U1") (pin "7") (pinfunction "VSS/VSSA_7") (pintype "passive"))
    )
    (net (code "53") (name "unconnected-(J1-TIP_SWITCH-Pad4)") (class "Default")
      (node (ref "J1") (pin "4") (pinfunction "TIP_SWITCH_4") (pintype "passive"))
    )
    (net (code "54") (name "unconnected-(U1-PA0-Pad11)") (class "Default")
      (node (ref "U1") (pin "11") (pinfunction "PA0_11") (pintype "bidirectional"))
    )
    (net (code "55") (name "unconnected-(U1-PA1-Pad12)") (class "Default")
      (node (ref "U1") (pin "12") (pinfunction "PA1_12") (pintype "bidirectional"))
    )
    (net (code "56") (name "unconnected-(U1-PA5-Pad16)") (class "Default")
      (node (ref "U1") (pin "16") (pinfunction "PA5_16") (pintype "bidirectional"))
    )
    (net (code "57") (name "unconnected-(U1-PA8-Pad28)") (class "Default")
      (node (ref "U1") (pin "28") (pinfunction "PA8_28") (pintype "bidirectional"))
    )
    (net (code "58") (name "unconnected-(U1-PA11_[PA9]-Pad33)") (class "Default")
      (node (ref "U1") (pin "33") (pinfunction "PA11_[PA9]_33") (pintype "bidirectional"))
    )
    (net (code "59") (name "unconnected-(U1-PA12_[PA10]-Pad34)") (class "Default")
      (node (ref "U1") (pin "34") (pinfunction "PA12_[PA10]_34") (pintype "bidirectional"))
    )
    (net (code "60") (name "unconnected-(U1-PA15-Pad37)") (class "Default")
      (node (ref "U1") (pin "37") (pinfunction "PA15_37") (pintype "bidirectional"))
    )
    (net (code "61") (name "unconnected-(U1-PB1-Pad20)") (class "Default")
      (node (ref "U1") (pin "20") (pinfunction "PB1_20") (pintype "bidirectional"))
    )
    (net (code "62") (name "unconnected-(U1-PB2-Pad21)") (class "Default")
      (node (ref "U1") (pin "21") (pinfunction "PB2_21") (pintype "bidirectional"))
    )
    (net (code "63") (name "unconnected-(U1-PB3-Pad42)") (class "Default")
      (node (ref "U1") (pin "42") (pinfunction "PB3_42") (pintype "bidirectional"))
    )
    (net (code "64") (name "unconnected-(U1-PB4-Pad43)") (class "Default")
      (node (ref "U1") (pin "43") (pinfunction "PB4_43") (pintype "bidirectional"))
    )
    (net (code "65") (name "unconnected-(U1-PB5-Pad44)") (class "Default")
      (node (ref "U1") (pin "44") (pinfunction "PB5_44") (pintype "bidirectional"))
    )
    (net (code "66") (name "unconnected-(U1-PB6-Pad45)") (class "Default")
      (node (ref "U1") (pin "45") (pinfunction "PB6_45") (pintype "bidirectional"))
    )
    (net (code "67") (name "unconnected-(U1-PB12-Pad24)") (class "Default")
      (node (ref "U1") (pin "24") (pinfunction "PB12_24") (pintype "bidirectional"))
    )
    (net (code "68") (name "unconnected-(U1-PB13-Pad25)") (class "Default")
      (node (ref "U1") (pin "25") (pinfunction "PB13_25") (pintype "bidirectional"))
    )
    (net (code "69") (name "unconnected-(U1-PB14-Pad26)") (class "Default")
      (node (ref "U1") (pin "26") (pinfunction "PB14_26") (pintype "bidirectional"))
    )
    (net (code "70") (name "unconnected-(U1-PB15-Pad27)") (class "Default")
      (node (ref "U1") (pin "27") (pinfunction "PB15_27") (pintype "bidirectional"))
    )
    (net (code "71") (name "unconnected-(U1-PC6-Pad30)") (class "Default")
      (node (ref "U1") (pin "30") (pinfunction "PC6_30") (pintype "bidirectional"))
    )
    (net (code "72") (name "unconnected-(U1-PC7-Pad31)") (class "Default")
      (node (ref "U1") (pin "31") (pinfunction "PC7_31") (pintype "bidirectional"))
    )
    (net (code "73") (name "unconnected-(U1-PC13-Pad1)") (class "Default")
      (node (ref "U1") (pin "1") (pinfunction "PC13_1") (pintype "bidirectional"))
    )
    (net (code "74") (name "unconnected-(U1-PC14-OSC32_IN-Pad2)") (class "Default")
      (node (ref "U1") (pin "2") (pinfunction "PC14-OSC32_IN_2") (pintype "bidirectional"))
    )
    (net (code "75") (name "unconnected-(U1-PC15-OSC32_OUT-Pad3)") (class "Default")
      (node (ref "U1") (pin "3") (pinfunction "PC15-OSC32_OUT_3") (pintype "output"))
    )
    (net (code "76") (name "unconnected-(U1-PD0-Pad38)") (class "Default")
      (node (ref "U1") (pin "38") (pinfunction "PD0_38") (pintype "bidirectional"))
    )
    (net (code "77") (name "unconnected-(U1-PD1-Pad39)") (class "Default")
      (node (ref "U1") (pin "39") (pinfunction "PD1_39") (pintype "bidirectional"))
    )
  )
)
